# oscillator.net
KiCad netlist of a schematic drawn in EAGLE
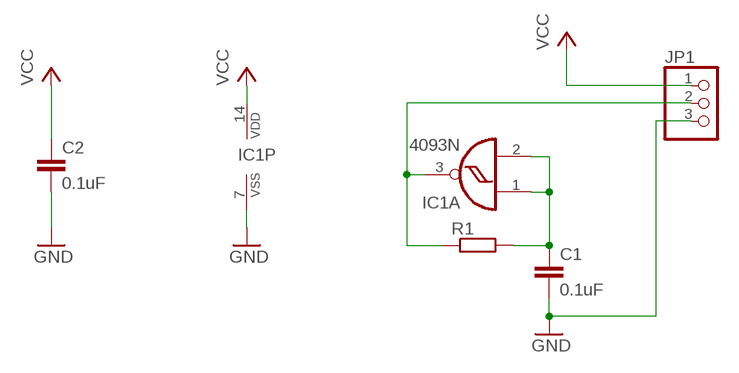
[diagram p0: schematic, sheet 1]

(export (version "E")
  (design (tool "Eeschema 10.0.6"))
  (components
    (comp (ref "C1")
      (value "0.1uF")
      (footprint "eagle-import:C025_050-025X075")
      (libsource (lib "eagle-import") (part "C-EU025_050-025X075"))
    )
    (comp (ref "C2")
      (value "0.1uF")
      (footprint "eagle-import:C025-025X050")
      (libsource (lib "eagle-import") (part "C-EU025-025X050"))
    )
    (comp (ref "IC1")
      (value "4093N")
      (footprint "eagle-import:DIL14")
      (libsource (lib "eagle-import") (part "4093N"))
    )
    (comp (ref "JP1")
      (value "PINHD-1X3")
      (footprint "eagle-import:1X03")
      (libsource (lib "eagle-import") (part "PINHD-1X3"))
    )
    (comp (ref "R1")
      (value "68K")
      (footprint "eagle-import:0204_7")
      (libsource (lib "eagle-import") (part "R-EU_0204/7"))
    )
  )
  (nets
    (net (code "1") (name "GND") (class "Default")
      (node (ref "C1") (pin "2") (pinfunction "2_2") (pintype "passive"))
      (node (ref "C2") (pin "2") (pinfunction "2_2") (pintype "passive"))
      (node (ref "IC1") (pin "7") (pinfunction "VSS_7") (pintype "power_in"))
      (node (ref "JP1") (pin "3") (pinfunction "3_3") (pintype "passive"))
    )
    (net (code "2") (name "Net-(IC1A-I0)") (class "Default")
      (node (ref "C1") (pin "1") (pinfunction "1_1") (pintype "passive"))
      (node (ref "IC1") (pin "1") (pinfunction "I0_1") (pintype "input"))
      (node (ref "IC1") (pin "2") (pinfunction "I1_2") (pintype "input"))
      (node (ref "R1") (pin "2") (pinfunction "2_2") (pintype "passive"))
    )
    (net (code "3") (name "Net-(IC1A-O)") (class "Default")
      (node (ref "IC1") (pin "3") (pinfunction "O_3") (pintype "output"))
      (node (ref "JP1") (pin "2") (pinfunction "2_2") (pintype "passive"))
      (node (ref "R1") (pin "1") (pinfunction "1_1") (pintype "passive"))
    )
    (net (code "4") (name "VCC") (class "Default")
      (node (ref "C2") (pin "1") (pinfunction "1_1") (pintype "passive"))
      (node (ref "IC1") (pin "14") (pinfunction "VDD_14") (pintype "power_in"))
      (node (ref "JP1") (pin "1") (pinfunction "1_1") (pintype "passive"))
    )
  )
)
